# 00_Main_Rev1.net
KiCad netlist of a schematic drawn in Altium Designer
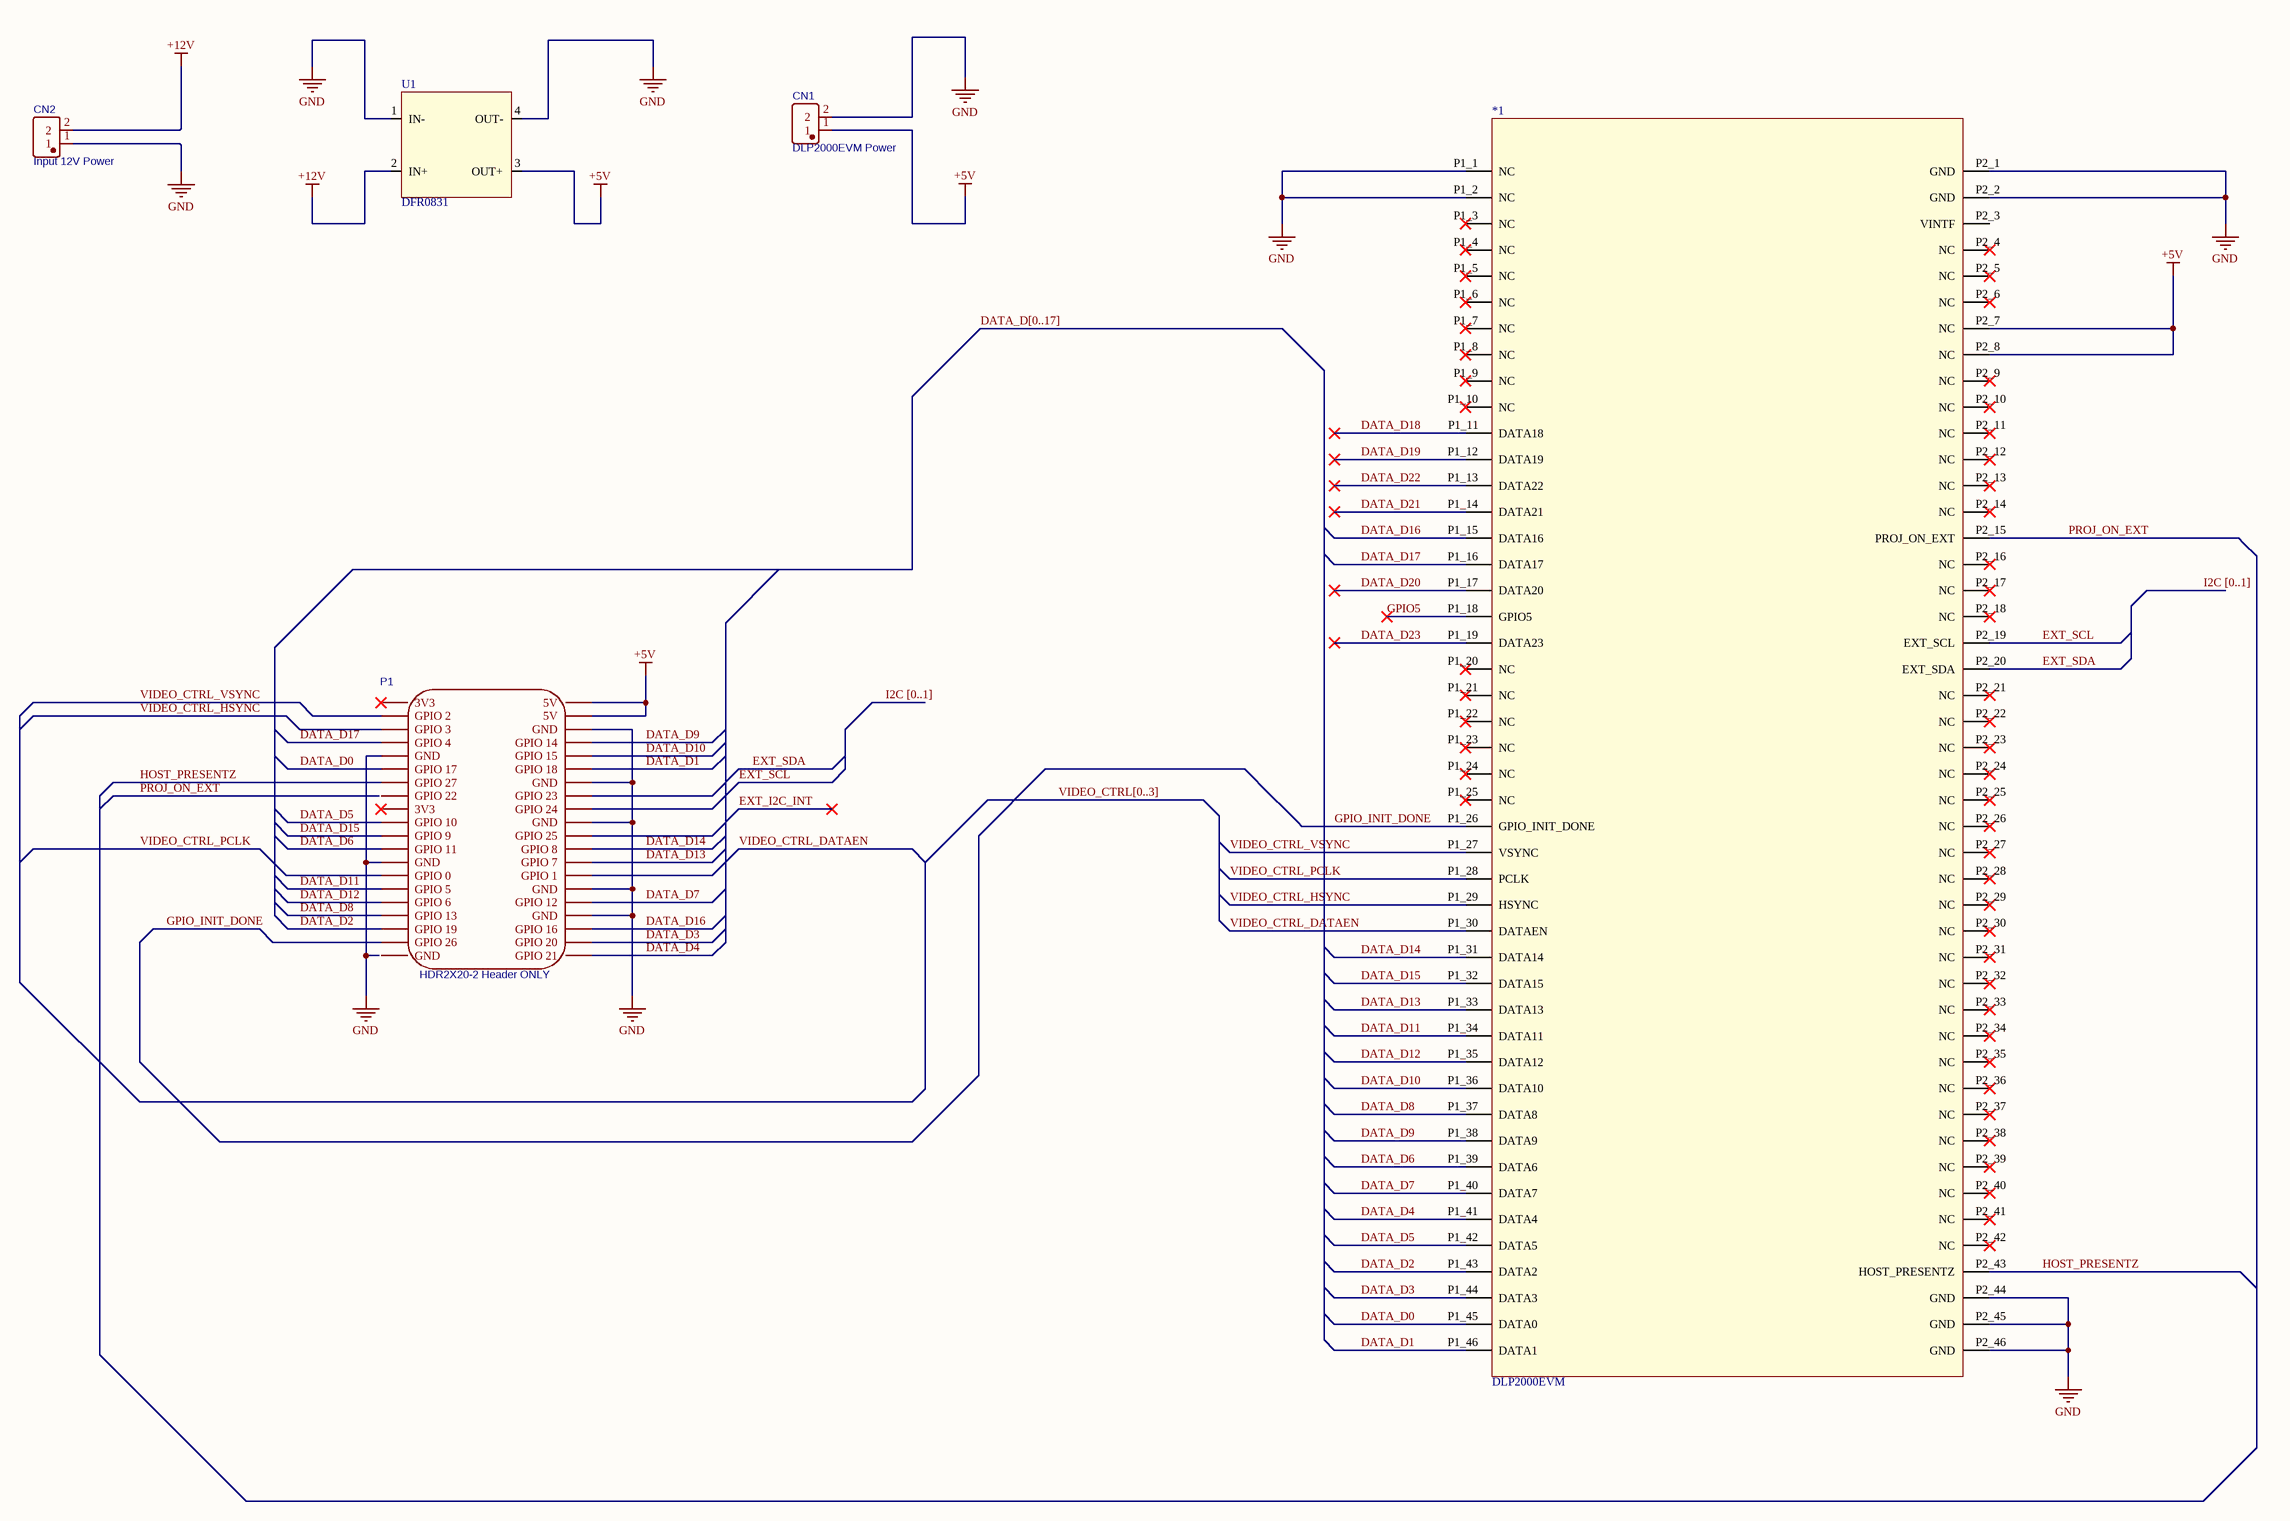
[diagram p0: 00_Main_Rev1.SchDoc]

(export (version "E")
  (design (tool "Eeschema 10.0.6"))
  (components
    (comp (ref "*1")
      (value "DLP2000EVM")
      (footprint "DLP_2000EVM")
      (libsource (lib "MyIntegratedLibrary_SCH") (part "DLP2000EVM"))
    )
    (comp (ref "CN1")
      (value "DLP2000EVM Power")
      (footprint "CONN-TH_2P-P2.54_JILN_JL141V-25402GA1")
      (fields
        (field (name "BOM_SUPPLIER PART") "C2922619")
        (field (name "BOM_MANUFACTURER PART") "JL141V-25402GA1")
        (field (name "CONTRIBUTOR") "LCSC")
      )
      (libsource (lib "MyIntegratedLibrary_SCH") (part "JL141V-25402GA1"))
    )
    (comp (ref "CN2")
      (value "Input 12V Power")
      (footprint "CONN-TH_2P-P2.54_JILN_JL141V-25402GA1")
      (fields
        (field (name "BOM_SUPPLIER PART") "C2922619")
        (field (name "BOM_MANUFACTURER PART") "JL141V-25402GA1")
        (field (name "CONTRIBUTOR") "LCSC")
      )
      (libsource (lib "MyIntegratedLibrary_SCH") (part "JL141V-25402GA1"))
    )
    (comp (ref "P1")
      (value "HDR2X20-2 Header ONLY")
      (footprint "Raspberry Pi A+")
      (description "Header Only")
      (libsource (lib "MyIntegratedLibrary_SCH") (part "Raspberry Pi A+"))
    )
    (comp (ref "U1")
      (value "DFR0831")
      (footprint "DFR0831")
      (description "DC-DC Buck Converter 7-24V to 5V 4A")
      (libsource (lib "MyIntegratedLibrary_SCH") (part "DFR0831"))
    )
  )
  (nets
    (net (code "5") (name "+5V") (class "Default")
      (node (ref "*1") (pin "P2_7") (pinfunction "NC_P2_7") (pintype "passive"))
      (node (ref "*1") (pin "P2_8") (pinfunction "NC_P2_8") (pintype "passive"))
      (node (ref "CN1") (pin "1") (pinfunction "1_1") (pintype "passive"))
      (node (ref "P1") (pin "2") (pinfunction "5V_2") (pintype "passive"))
      (node (ref "P1") (pin "4") (pinfunction "5V_4") (pintype "passive"))
      (node (ref "U1") (pin "3") (pinfunction "OUT+_3") (pintype "passive"))
    )
    (net (code "6") (name "+12V") (class "Default")
      (node (ref "CN2") (pin "2") (pinfunction "2_2") (pintype "passive"))
      (node (ref "U1") (pin "2") (pinfunction "IN+_2") (pintype "passive"))
    )
    (net (code "7") (name "/DATA_D0") (class "Default")
      (node (ref "*1") (pin "P1_45") (pinfunction "DATA0_P1_45") (pintype "passive"))
      (node (ref "P1") (pin "11") (pinfunction "GPIO_17_11") (pintype "passive"))
    )
    (net (code "8") (name "/DATA_D1") (class "Default")
      (node (ref "*1") (pin "P1_46") (pinfunction "DATA1_P1_46") (pintype "passive"))
      (node (ref "P1") (pin "12") (pinfunction "GPIO_18_12") (pintype "passive"))
    )
    (net (code "9") (name "/DATA_D2") (class "Default")
      (node (ref "*1") (pin "P1_43") (pinfunction "DATA2_P1_43") (pintype "passive"))
      (node (ref "P1") (pin "35") (pinfunction "GPIO_19_35") (pintype "passive"))
    )
    (net (code "10") (name "/DATA_D3") (class "Default")
      (node (ref "*1") (pin "P1_44") (pinfunction "DATA3_P1_44") (pintype "passive"))
      (node (ref "P1") (pin "38") (pinfunction "GPIO_20_38") (pintype "passive"))
    )
    (net (code "11") (name "/DATA_D4") (class "Default")
      (node (ref "*1") (pin "P1_41") (pinfunction "DATA4_P1_41") (pintype "passive"))
      (node (ref "P1") (pin "40") (pinfunction "GPIO_21_40") (pintype "passive"))
    )
    (net (code "12") (name "/DATA_D5") (class "Default")
      (node (ref "*1") (pin "P1_42") (pinfunction "DATA5_P1_42") (pintype "passive"))
      (node (ref "P1") (pin "19") (pinfunction "GPIO_10_19") (pintype "passive"))
    )
    (net (code "13") (name "/DATA_D6") (class "Default")
      (node (ref "*1") (pin "P1_39") (pinfunction "DATA6_P1_39") (pintype "passive"))
      (node (ref "P1") (pin "23") (pinfunction "GPIO_11_23") (pintype "passive"))
    )
    (net (code "14") (name "/DATA_D7") (class "Default")
      (node (ref "*1") (pin "P1_40") (pinfunction "DATA7_P1_40") (pintype "passive"))
      (node (ref "P1") (pin "32") (pinfunction "GPIO_12_32") (pintype "passive"))
    )
    (net (code "15") (name "/DATA_D8") (class "Default")
      (node (ref "*1") (pin "P1_37") (pinfunction "DATA8_P1_37") (pintype "passive"))
      (node (ref "P1") (pin "33") (pinfunction "GPIO_13_33") (pintype "passive"))
    )
    (net (code "16") (name "/DATA_D9") (class "Default")
      (node (ref "*1") (pin "P1_38") (pinfunction "DATA9_P1_38") (pintype "passive"))
      (node (ref "P1") (pin "8") (pinfunction "GPIO_14_8") (pintype "passive"))
    )
    (net (code "17") (name "/DATA_D10") (class "Default")
      (node (ref "*1") (pin "P1_36") (pinfunction "DATA10_P1_36") (pintype "passive"))
      (node (ref "P1") (pin "10") (pinfunction "GPIO_15_10") (pintype "passive"))
    )
    (net (code "18") (name "/DATA_D11") (class "Default")
      (node (ref "*1") (pin "P1_34") (pinfunction "DATA11_P1_34") (pintype "passive"))
      (node (ref "P1") (pin "29") (pinfunction "GPIO_5_29") (pintype "passive"))
    )
    (net (code "19") (name "/DATA_D12") (class "Default")
      (node (ref "*1") (pin "P1_35") (pinfunction "DATA12_P1_35") (pintype "passive"))
      (node (ref "P1") (pin "31") (pinfunction "GPIO_6_31") (pintype "passive"))
    )
    (net (code "20") (name "/DATA_D13") (class "Default")
      (node (ref "*1") (pin "P1_33") (pinfunction "DATA13_P1_33") (pintype "passive"))
      (node (ref "P1") (pin "26") (pinfunction "GPIO_7_26") (pintype "passive"))
    )
    (net (code "21") (name "/DATA_D14") (class "Default")
      (node (ref "*1") (pin "P1_31") (pinfunction "DATA14_P1_31") (pintype "passive"))
      (node (ref "P1") (pin "24") (pinfunction "GPIO_8_24") (pintype "passive"))
    )
    (net (code "22") (name "/DATA_D15") (class "Default")
      (node (ref "*1") (pin "P1_32") (pinfunction "DATA15_P1_32") (pintype "passive"))
      (node (ref "P1") (pin "21") (pinfunction "GPIO_9_21") (pintype "passive"))
    )
    (net (code "23") (name "/DATA_D16") (class "Default")
      (node (ref "*1") (pin "P1_15") (pinfunction "DATA16_P1_15") (pintype "passive"))
      (node (ref "P1") (pin "36") (pinfunction "GPIO_16_36") (pintype "passive"))
    )
    (net (code "24") (name "/DATA_D17") (class "Default")
      (node (ref "*1") (pin "P1_16") (pinfunction "DATA17_P1_16") (pintype "passive"))
      (node (ref "P1") (pin "7") (pinfunction "GPIO_4_7") (pintype "passive"))
    )
    (net (code "25") (name "/DATA_D18") (class "Default")
      (node (ref "*1") (pin "P1_11") (pinfunction "DATA18_P1_11") (pintype "passive+no_connect"))
    )
    (net (code "26") (name "/DATA_D19") (class "Default")
      (node (ref "*1") (pin "P1_12") (pinfunction "DATA19_P1_12") (pintype "passive+no_connect"))
    )
    (net (code "27") (name "/DATA_D20") (class "Default")
      (node (ref "*1") (pin "P1_17") (pinfunction "DATA20_P1_17") (pintype "passive+no_connect"))
    )
    (net (code "28") (name "/DATA_D21") (class "Default")
      (node (ref "*1") (pin "P1_14") (pinfunction "DATA21_P1_14") (pintype "passive+no_connect"))
    )
    (net (code "29") (name "/DATA_D22") (class "Default")
      (node (ref "*1") (pin "P1_13") (pinfunction "DATA22_P1_13") (pintype "passive+no_connect"))
    )
    (net (code "30") (name "/DATA_D23") (class "Default")
      (node (ref "*1") (pin "P1_19") (pinfunction "DATA23_P1_19") (pintype "passive+no_connect"))
    )
    (net (code "32") (name "/EXT_I2C_INT") (class "Default")
      (node (ref "P1") (pin "22") (pinfunction "GPIO_25_22") (pintype "passive+no_connect"))
    )
    (net (code "33") (name "/EXT_SCL") (class "Default")
      (node (ref "*1") (pin "P2_19") (pinfunction "EXT_SCL_P2_19") (pintype "passive"))
      (node (ref "P1") (pin "18") (pinfunction "GPIO_24_18") (pintype "passive"))
    )
    (net (code "34") (name "/EXT_SDA") (class "Default")
      (node (ref "*1") (pin "P2_20") (pinfunction "EXT_SDA_P2_20") (pintype "passive"))
      (node (ref "P1") (pin "16") (pinfunction "GPIO_23_16") (pintype "passive"))
    )
    (net (code "35") (name "/GPIO5") (class "Default")
      (node (ref "*1") (pin "P1_18") (pinfunction "GPIO5_P1_18") (pintype "passive+no_connect"))
    )
    (net (code "36") (name "/GPIO_INIT_DONE") (class "Default")
      (node (ref "*1") (pin "P1_26") (pinfunction "GPIO_INIT_DONE_P1_26") (pintype "passive"))
      (node (ref "P1") (pin "37") (pinfunction "GPIO_26_37") (pintype "passive"))
    )
    (net (code "37") (name "/HOST_PRESENTZ") (class "Default")
      (node (ref "*1") (pin "P2_43") (pinfunction "HOST_PRESENTZ_P2_43") (pintype "passive"))
      (node (ref "P1") (pin "13") (pinfunction "GPIO_27_13") (pintype "passive"))
    )
    (net (code "38") (name "/PROJ_ON_EXT") (class "Default")
      (node (ref "*1") (pin "P2_15") (pinfunction "PROJ_ON_EXT_P2_15") (pintype "passive"))
    )
    (net (code "40") (name "/VIDEO_CTRL_DATAEN") (class "Default")
      (node (ref "*1") (pin "P1_30") (pinfunction "DATAEN_P1_30") (pintype "passive"))
      (node (ref "P1") (pin "28") (pinfunction "GPIO_1_28") (pintype "passive"))
    )
    (net (code "41") (name "/VIDEO_CTRL_HSYNC") (class "Default")
      (node (ref "*1") (pin "P1_29") (pinfunction "HSYNC_P1_29") (pintype "passive"))
      (node (ref "P1") (pin "5") (pinfunction "GPIO_3_5") (pintype "passive"))
    )
    (net (code "42") (name "/VIDEO_CTRL_PCLK") (class "Default")
      (node (ref "*1") (pin "P1_28") (pinfunction "PCLK_P1_28") (pintype "passive"))
      (node (ref "P1") (pin "27") (pinfunction "GPIO_0_27") (pintype "passive"))
    )
    (net (code "43") (name "/VIDEO_CTRL_VSYNC") (class "Default")
      (node (ref "*1") (pin "P1_27") (pinfunction "VSYNC_P1_27") (pintype "passive"))
      (node (ref "P1") (pin "3") (pinfunction "GPIO_2_3") (pintype "passive"))
    )
    (net (code "45") (name "GND") (class "Default")
      (node (ref "*1") (pin "P1_1") (pinfunction "NC_P1_1") (pintype "passive"))
      (node (ref "*1") (pin "P1_2") (pinfunction "NC_P1_2") (pintype "passive"))
      (node (ref "*1") (pin "P2_1") (pinfunction "GND_P2_1") (pintype "passive"))
      (node (ref "*1") (pin "P2_2") (pinfunction "GND_P2_2") (pintype "passive"))
      (node (ref "*1") (pin "P2_44") (pinfunction "GND_P2_44") (pintype "passive"))
      (node (ref "*1") (pin "P2_45") (pinfunction "GND_P2_45") (pintype "passive"))
      (node (ref "*1") (pin "P2_46") (pinfunction "GND_P2_46") (pintype "passive"))
      (node (ref "CN1") (pin "2") (pinfunction "2_2") (pintype "passive"))
      (node (ref "CN2") (pin "1") (pinfunction "1_1") (pintype "passive"))
      (node (ref "P1") (pin "14") (pinfunction "GND_14") (pintype "passive"))
      (node (ref "P1") (pin "20") (pinfunction "GND_20") (pintype "passive"))
      (node (ref "P1") (pin "25") (pinfunction "GND_25") (pintype "passive"))
      (node (ref "P1") (pin "30") (pinfunction "GND_30") (pintype "passive"))
      (node (ref "P1") (pin "34") (pinfunction "GND_34") (pintype "passive"))
      (node (ref "P1") (pin "6") (pinfunction "GND_6") (pintype "passive"))
      (node (ref "P1") (pin "9") (pinfunction "GND_9") (pintype "passive"))
      (node (ref "U1") (pin "1") (pinfunction "IN-_1") (pintype "passive"))
      (node (ref "U1") (pin "4") (pinfunction "OUT-_4") (pintype "passive"))
    )
    (net (code "46") (name "unconnected-(*1-NC-PadP1_3)") (class "Default")
      (node (ref "*1") (pin "P1_3") (pinfunction "NC_P1_3") (pintype "passive+no_connect"))
    )
    (net (code "47") (name "unconnected-(*1-NC-PadP1_4)") (class "Default")
      (node (ref "*1") (pin "P1_4") (pinfunction "NC_P1_4") (pintype "passive+no_connect"))
    )
    (net (code "48") (name "unconnected-(*1-NC-PadP1_5)") (class "Default")
      (node (ref "*1") (pin "P1_5") (pinfunction "NC_P1_5") (pintype "passive+no_connect"))
    )
    (net (code "49") (name "unconnected-(*1-NC-PadP1_6)") (class "Default")
      (node (ref "*1") (pin "P1_6") (pinfunction "NC_P1_6") (pintype "passive+no_connect"))
    )
    (net (code "50") (name "unconnected-(*1-NC-PadP1_7)") (class "Default")
      (node (ref "*1") (pin "P1_7") (pinfunction "NC_P1_7") (pintype "passive+no_connect"))
    )
    (net (code "51") (name "unconnected-(*1-NC-PadP1_8)") (class "Default")
      (node (ref "*1") (pin "P1_8") (pinfunction "NC_P1_8") (pintype "passive+no_connect"))
    )
    (net (code "52") (name "unconnected-(*1-NC-PadP1_9)") (class "Default")
      (node (ref "*1") (pin "P1_9") (pinfunction "NC_P1_9") (pintype "passive+no_connect"))
    )
    (net (code "53") (name "unconnected-(*1-NC-PadP1_10)") (class "Default")
      (node (ref "*1") (pin "P1_10") (pinfunction "NC_P1_10") (pintype "passive+no_connect"))
    )
    (net (code "54") (name "unconnected-(*1-NC-PadP1_20)") (class "Default")
      (node (ref "*1") (pin "P1_20") (pinfunction "NC_P1_20") (pintype "passive+no_connect"))
    )
    (net (code "55") (name "unconnected-(*1-NC-PadP1_21)") (class "Default")
      (node (ref "*1") (pin "P1_21") (pinfunction "NC_P1_21") (pintype "passive+no_connect"))
    )
    (net (code "56") (name "unconnected-(*1-NC-PadP1_22)") (class "Default")
      (node (ref "*1") (pin "P1_22") (pinfunction "NC_P1_22") (pintype "passive+no_connect"))
    )
    (net (code "57") (name "unconnected-(*1-NC-PadP1_23)") (class "Default")
      (node (ref "*1") (pin "P1_23") (pinfunction "NC_P1_23") (pintype "passive+no_connect"))
    )
    (net (code "58") (name "unconnected-(*1-NC-PadP1_24)") (class "Default")
      (node (ref "*1") (pin "P1_24") (pinfunction "NC_P1_24") (pintype "passive+no_connect"))
    )
    (net (code "59") (name "unconnected-(*1-NC-PadP1_25)") (class "Default")
      (node (ref "*1") (pin "P1_25") (pinfunction "NC_P1_25") (pintype "passive+no_connect"))
    )
    (net (code "60") (name "unconnected-(*1-NC-PadP2_4)") (class "Default")
      (node (ref "*1") (pin "P2_4") (pinfunction "NC_P2_4") (pintype "passive+no_connect"))
    )
    (net (code "61") (name "unconnected-(*1-NC-PadP2_5)") (class "Default")
      (node (ref "*1") (pin "P2_5") (pinfunction "NC_P2_5") (pintype "passive+no_connect"))
    )
    (net (code "62") (name "unconnected-(*1-NC-PadP2_6)") (class "Default")
      (node (ref "*1") (pin "P2_6") (pinfunction "NC_P2_6") (pintype "passive+no_connect"))
    )
    (net (code "63") (name "unconnected-(*1-NC-PadP2_9)") (class "Default")
      (node (ref "*1") (pin "P2_9") (pinfunction "NC_P2_9") (pintype "passive+no_connect"))
    )
    (net (code "64") (name "unconnected-(*1-NC-PadP2_10)") (class "Default")
      (node (ref "*1") (pin "P2_10") (pinfunction "NC_P2_10") (pintype "passive+no_connect"))
    )
    (net (code "65") (name "unconnected-(*1-NC-PadP2_11)") (class "Default")
      (node (ref "*1") (pin "P2_11") (pinfunction "NC_P2_11") (pintype "passive+no_connect"))
    )
    (net (code "66") (name "unconnected-(*1-NC-PadP2_12)") (class "Default")
      (node (ref "*1") (pin "P2_12") (pinfunction "NC_P2_12") (pintype "passive+no_connect"))
    )
    (net (code "67") (name "unconnected-(*1-NC-PadP2_13)") (class "Default")
      (node (ref "*1") (pin "P2_13") (pinfunction "NC_P2_13") (pintype "passive+no_connect"))
    )
    (net (code "68") (name "unconnected-(*1-NC-PadP2_14)") (class "Default")
      (node (ref "*1") (pin "P2_14") (pinfunction "NC_P2_14") (pintype "passive+no_connect"))
    )
    (net (code "69") (name "unconnected-(*1-NC-PadP2_16)") (class "Default")
      (node (ref "*1") (pin "P2_16") (pinfunction "NC_P2_16") (pintype "passive+no_connect"))
    )
    (net (code "70") (name "unconnected-(*1-NC-PadP2_17)") (class "Default")
      (node (ref "*1") (pin "P2_17") (pinfunction "NC_P2_17") (pintype "passive+no_connect"))
    )
    (net (code "71") (name "unconnected-(*1-NC-PadP2_18)") (class "Default")
      (node (ref "*1") (pin "P2_18") (pinfunction "NC_P2_18") (pintype "passive+no_connect"))
    )
    (net (code "72") (name "unconnected-(*1-NC-PadP2_21)") (class "Default")
      (node (ref "*1") (pin "P2_21") (pinfunction "NC_P2_21") (pintype "passive+no_connect"))
    )
    (net (code "73") (name "unconnected-(*1-NC-PadP2_22)") (class "Default")
      (node (ref "*1") (pin "P2_22") (pinfunction "NC_P2_22") (pintype "passive+no_connect"))
    )
    (net (code "74") (name "unconnected-(*1-NC-PadP2_23)") (class "Default")
      (node (ref "*1") (pin "P2_23") (pinfunction "NC_P2_23") (pintype "passive+no_connect"))
    )
    (net (code "75") (name "unconnected-(*1-NC-PadP2_24)") (class "Default")
      (node (ref "*1") (pin "P2_24") (pinfunction "NC_P2_24") (pintype "passive+no_connect"))
    )
    (net (code "76") (name "unconnected-(*1-NC-PadP2_25)") (class "Default")
      (node (ref "*1") (pin "P2_25") (pinfunction "NC_P2_25") (pintype "passive+no_connect"))
    )
    (net (code "77") (name "unconnected-(*1-NC-PadP2_26)") (class "Default")
      (node (ref "*1") (pin "P2_26") (pinfunction "NC_P2_26") (pintype "passive+no_connect"))
    )
    (net (code "78") (name "unconnected-(*1-NC-PadP2_27)") (class "Default")
      (node (ref "*1") (pin "P2_27") (pinfunction "NC_P2_27") (pintype "passive+no_connect"))
    )
    (net (code "79") (name "unconnected-(*1-NC-PadP2_28)") (class "Default")
      (node (ref "*1") (pin "P2_28") (pinfunction "NC_P2_28") (pintype "passive+no_connect"))
    )
    (net (code "80") (name "unconnected-(*1-NC-PadP2_29)") (class "Default")
      (node (ref "*1") (pin "P2_29") (pinfunction "NC_P2_29") (pintype "passive+no_connect"))
    )
    (net (code "81") (name "unconnected-(*1-NC-PadP2_30)") (class "Default")
      (node (ref "*1") (pin "P2_30") (pinfunction "NC_P2_30") (pintype "passive+no_connect"))
    )
    (net (code "82") (name "unconnected-(*1-NC-PadP2_31)") (class "Default")
      (node (ref "*1") (pin "P2_31") (pinfunction "NC_P2_31") (pintype "passive+no_connect"))
    )
    (net (code "83") (name "unconnected-(*1-NC-PadP2_32)") (class "Default")
      (node (ref "*1") (pin "P2_32") (pinfunction "NC_P2_32") (pintype "passive+no_connect"))
    )
    (net (code "84") (name "unconnected-(*1-NC-PadP2_33)") (class "Default")
      (node (ref "*1") (pin "P2_33") (pinfunction "NC_P2_33") (pintype "passive+no_connect"))
    )
    (net (code "85") (name "unconnected-(*1-NC-PadP2_34)") (class "Default")
      (node (ref "*1") (pin "P2_34") (pinfunction "NC_P2_34") (pintype "passive+no_connect"))
    )
    (net (code "86") (name "unconnected-(*1-NC-PadP2_35)") (class "Default")
      (node (ref "*1") (pin "P2_35") (pinfunction "NC_P2_35") (pintype "passive+no_connect"))
    )
    (net (code "87") (name "unconnected-(*1-NC-PadP2_36)") (class "Default")
      (node (ref "*1") (pin "P2_36") (pinfunction "NC_P2_36") (pintype "passive+no_connect"))
    )
    (net (code "88") (name "unconnected-(*1-NC-PadP2_37)") (class "Default")
      (node (ref "*1") (pin "P2_37") (pinfunction "NC_P2_37") (pintype "passive+no_connect"))
    )
    (net (code "89") (name "unconnected-(*1-NC-PadP2_38)") (class "Default")
      (node (ref "*1") (pin "P2_38") (pinfunction "NC_P2_38") (pintype "passive+no_connect"))
    )
    (net (code "90") (name "unconnected-(*1-NC-PadP2_39)") (class "Default")
      (node (ref "*1") (pin "P2_39") (pinfunction "NC_P2_39") (pintype "passive+no_connect"))
    )
    (net (code "91") (name "unconnected-(*1-NC-PadP2_40)") (class "Default")
      (node (ref "*1") (pin "P2_40") (pinfunction "NC_P2_40") (pintype "passive+no_connect"))
    )
    (net (code "92") (name "unconnected-(*1-NC-PadP2_41)") (class "Default")
      (node (ref "*1") (pin "P2_41") (pinfunction "NC_P2_41") (pintype "passive+no_connect"))
    )
    (net (code "93") (name "unconnected-(*1-NC-PadP2_42)") (class "Default")
      (node (ref "*1") (pin "P2_42") (pinfunction "NC_P2_42") (pintype "passive+no_connect"))
    )
    (net (code "94") (name "unconnected-(*1-VINTF-PadP2_3)") (class "Default")
      (node (ref "*1") (pin "P2_3") (pinfunction "VINTF_P2_3") (pintype "passive"))
    )
    (net (code "95") (name "unconnected-(P1-3V3-Pad1)") (class "Default")
      (node (ref "P1") (pin "1") (pinfunction "3V3_1") (pintype "passive+no_connect"))
    )
    (net (code "96") (name "unconnected-(P1-3V3-Pad17)") (class "Default")
      (node (ref "P1") (pin "17") (pinfunction "3V3_17") (pintype "passive+no_connect"))
    )
    (net (code "97") (name "unconnected-(P1-GND-Pad39)") (class "Default")
      (node (ref "P1") (pin "39") (pinfunction "GND_39") (pintype "passive"))
    )
    (net (code "98") (name "unconnected-(P1-GPIO_22-Pad15)") (class "Default")
      (node (ref "P1") (pin "15") (pinfunction "GPIO_22_15") (pintype "passive"))
    )
  )
)
